# connectWing.net
KiCad netlist of a schematic drawn in EAGLE
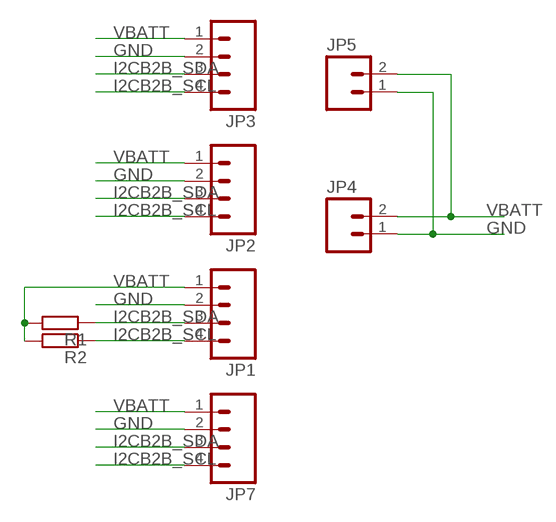
[diagram p0: schematic, sheet 1]

(export (version "E")
  (design (tool "Eeschema 10.0.6"))
  (components
    (comp (ref "JP1")
      (value "M04JST")
      (footprint "eagle-import:1X04-1.5MM_JST")
      (libsource (lib "eagle-import") (part "M04JST"))
    )
    (comp (ref "JP2")
      (value "M04JST")
      (footprint "eagle-import:1X04-1.5MM_JST")
      (libsource (lib "eagle-import") (part "M04JST"))
    )
    (comp (ref "JP3")
      (value "M04JST")
      (footprint "eagle-import:1X04-1.5MM_JST")
      (libsource (lib "eagle-import") (part "M04JST"))
    )
    (comp (ref "JP4")
      (value "M021X02_NO_SILK")
      (footprint "eagle-import:1X02_NO_SILK")
      (libsource (lib "eagle-import") (part "M021X02_NO_SILK"))
    )
    (comp (ref "JP5")
      (value "M021X02_NO_SILK")
      (footprint "eagle-import:1X02_NO_SILK")
      (libsource (lib "eagle-import") (part "M021X02_NO_SILK"))
    )
    (comp (ref "JP7")
      (value "M04JST")
      (footprint "eagle-import:1X04-1.5MM_JST")
      (libsource (lib "eagle-import") (part "M04JST"))
    )
    (comp (ref "R1")
      (value "R0805")
      (footprint "eagle-import:R0805")
      (libsource (lib "eagle-import") (part "R0805"))
    )
    (comp (ref "R2")
      (value "R0805")
      (footprint "eagle-import:R0805")
      (libsource (lib "eagle-import") (part "R0805"))
    )
  )
  (nets
    (net (code "1") (name "/GND") (class "Default")
      (node (ref "JP1") (pin "2") (pinfunction "2_2") (pintype "passive"))
      (node (ref "JP2") (pin "2") (pinfunction "2_2") (pintype "passive"))
      (node (ref "JP3") (pin "2") (pinfunction "2_2") (pintype "passive"))
      (node (ref "JP4") (pin "1") (pinfunction "1_1") (pintype "passive"))
      (node (ref "JP5") (pin "1") (pinfunction "1_1") (pintype "passive"))
      (node (ref "JP7") (pin "2") (pinfunction "2_2") (pintype "passive"))
    )
    (net (code "2") (name "/I2CB2B_SCL") (class "Default")
      (node (ref "JP1") (pin "4") (pinfunction "4_4") (pintype "passive"))
      (node (ref "JP2") (pin "4") (pinfunction "4_4") (pintype "passive"))
      (node (ref "JP3") (pin "4") (pinfunction "4_4") (pintype "passive"))
      (node (ref "JP7") (pin "4") (pinfunction "4_4") (pintype "passive"))
      (node (ref "R2") (pin "1") (pinfunction "1_1") (pintype "passive"))
    )
    (net (code "3") (name "/I2CB2B_SDA") (class "Default")
      (node (ref "JP1") (pin "3") (pinfunction "3_3") (pintype "passive"))
      (node (ref "JP2") (pin "3") (pinfunction "3_3") (pintype "passive"))
      (node (ref "JP3") (pin "3") (pinfunction "3_3") (pintype "passive"))
      (node (ref "JP7") (pin "3") (pinfunction "3_3") (pintype "passive"))
      (node (ref "R1") (pin "1") (pinfunction "1_1") (pintype "passive"))
    )
    (net (code "4") (name "/VBATT") (class "Default")
      (node (ref "JP1") (pin "1") (pinfunction "1_1") (pintype "passive"))
      (node (ref "JP2") (pin "1") (pinfunction "1_1") (pintype "passive"))
      (node (ref "JP3") (pin "1") (pinfunction "1_1") (pintype "passive"))
      (node (ref "JP4") (pin "2") (pinfunction "2_2") (pintype "passive"))
      (node (ref "JP5") (pin "2") (pinfunction "2_2") (pintype "passive"))
      (node (ref "JP7") (pin "1") (pinfunction "1_1") (pintype "passive"))
      (node (ref "R1") (pin "2") (pinfunction "2_2") (pintype "passive"))
      (node (ref "R2") (pin "2") (pinfunction "2_2") (pintype "passive"))
    )
  )
)
